# WL_BPF.net
KiCad netlist of a schematic drawn in Altium Designer
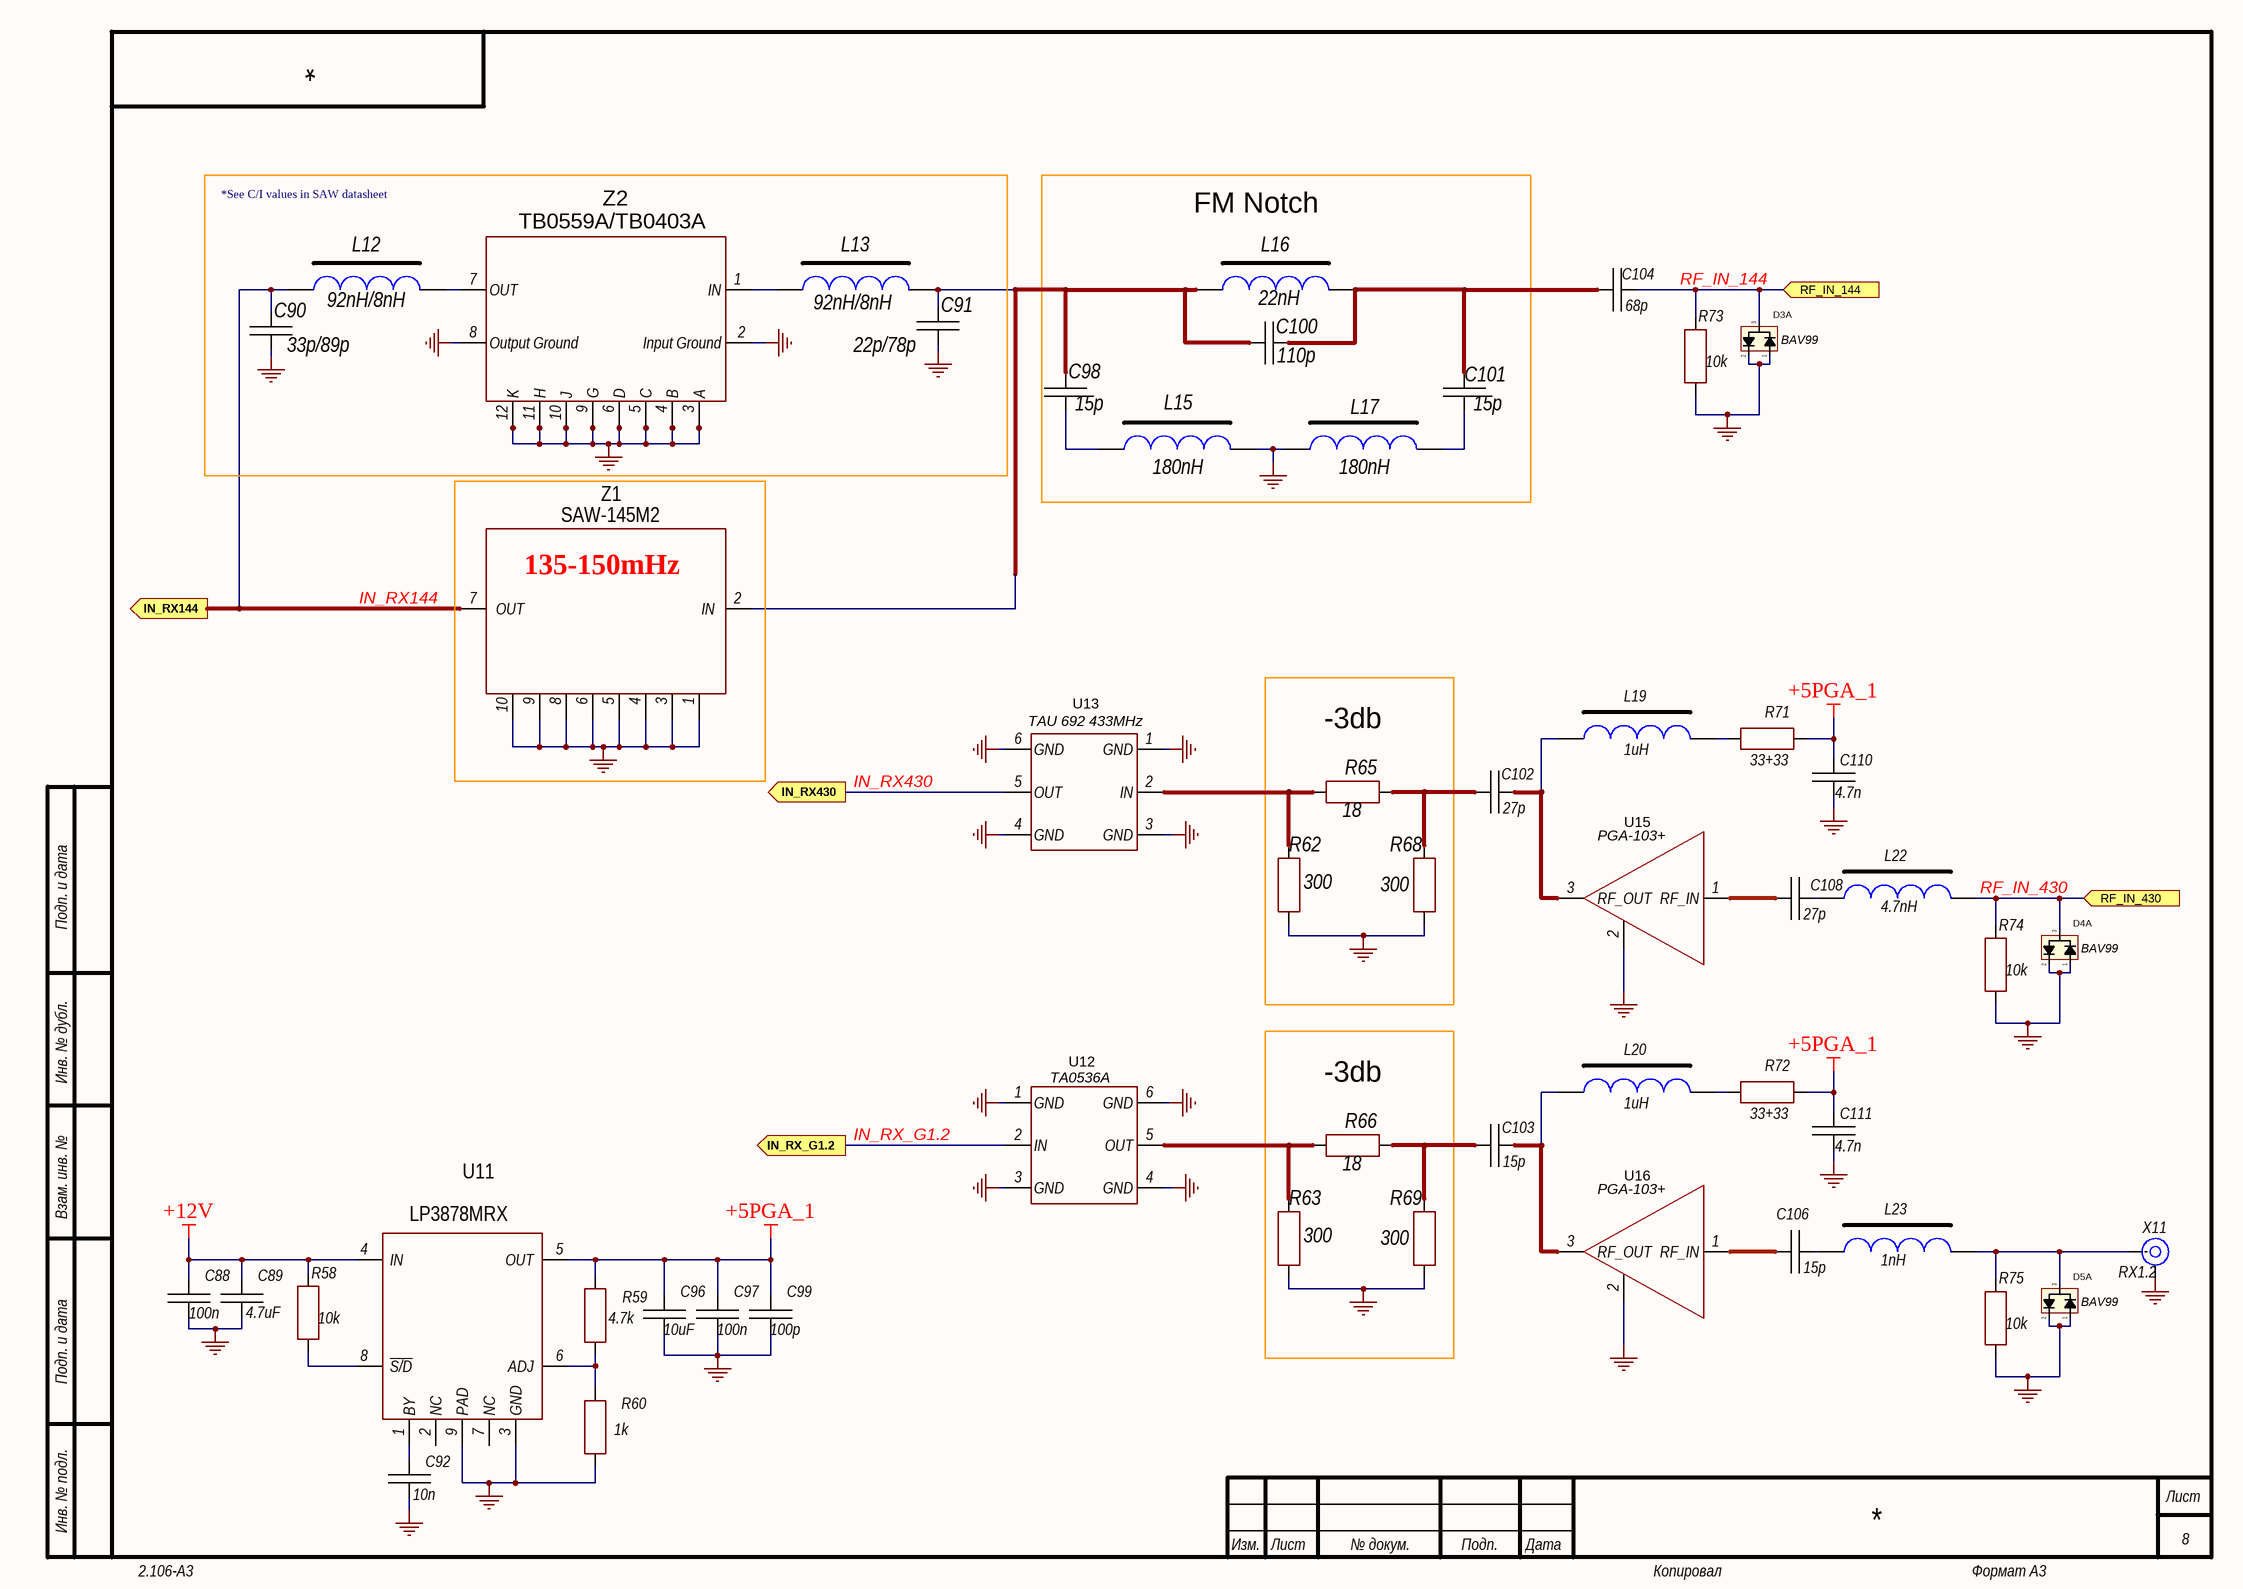
[diagram p0: WL_BPF.SchDoc]

(export (version "E")
  (design (tool "Eeschema 10.0.6"))
  (components
    (comp (ref "C88")
      (value "100n")
      (footprint "standard:CH0805C")
      (libsource (lib "Discrete") (part "Capacitor"))
    )
    (comp (ref "C89")
      (value "4.7uF")
      (footprint "standard:CH0805C")
      (libsource (lib "Discrete") (part "Capacitor"))
    )
    (comp (ref "C90")
      (value "33p/89p")
      (footprint "standard:CH0805C")
      (libsource (lib "Discrete") (part "Capacitor"))
    )
    (comp (ref "C91")
      (value "22p/78p")
      (footprint "standard:CH0805C")
      (libsource (lib "Discrete") (part "Capacitor"))
    )
    (comp (ref "C92")
      (value "10n")
      (footprint "standard:CH0805C")
      (libsource (lib "Discrete") (part "Capacitor"))
    )
    (comp (ref "C96")
      (value "10uF")
      (footprint "standard:CH0805C")
      (libsource (lib "Discrete") (part "Capacitor"))
    )
    (comp (ref "C97")
      (value "100n")
      (footprint "standard:CH0805C")
      (libsource (lib "Discrete") (part "Capacitor"))
    )
    (comp (ref "C98")
      (value "15p")
      (footprint "standard:CH0805C")
      (libsource (lib "Discrete") (part "Capacitor"))
    )
    (comp (ref "C99")
      (value "100p")
      (footprint "standard:CH0805C")
      (libsource (lib "Discrete") (part "Capacitor"))
    )
    (comp (ref "C100")
      (value "110p")
      (footprint "standard:CH0805C")
      (libsource (lib "Discrete") (part "Capacitor"))
    )
    (comp (ref "C101")
      (value "15p")
      (footprint "standard:CH0805C")
      (libsource (lib "Discrete") (part "Capacitor"))
    )
    (comp (ref "C102")
      (value "27p")
      (footprint "standard:CH0805C")
      (libsource (lib "Discrete") (part "Capacitor"))
    )
    (comp (ref "C103") (value "15p") (footprint "standard:CH0603C") (libsource (lib "") (part "Capacitor_1")))
    (comp (ref "C104")
      (value "68p")
      (footprint "standard:CH0805C")
      (libsource (lib "Discrete") (part "Capacitor"))
    )
    (comp (ref "C106") (value "15p") (footprint "standard:CH0603C") (libsource (lib "") (part "Capacitor_1")))
    (comp (ref "C108")
      (value "27p")
      (footprint "standard:CH0805C")
      (libsource (lib "Discrete") (part "Capacitor"))
    )
    (comp (ref "C110")
      (value "4.7n")
      (footprint "standard:CH0805C")
      (libsource (lib "Discrete") (part "Capacitor"))
    )
    (comp (ref "C111")
      (value "4.7n")
      (footprint "standard:CH0805C")
      (libsource (lib "Discrete") (part "Capacitor"))
    )
    (comp (ref "D3") (value "BAV99") (footprint "SOT23_132") (libsource (lib "Analog") (part "BAV99")))
    (comp (ref "D4") (value "BAV99") (footprint "SOT23_132") (libsource (lib "Analog") (part "BAV99")))
    (comp (ref "D5") (value "BAV99") (footprint "SOT23_132") (libsource (lib "Analog") (part "BAV99")))
    (comp (ref "L12") (value "92nH/8nH") (footprint "L1210") (libsource (lib "Transformers") (part "TRANS")))
    (comp (ref "L13") (value "92nH/8nH") (footprint "L1210") (libsource (lib "Transformers") (part "TRANS")))
    (comp (ref "L15") (value "180nH") (footprint "L1210") (libsource (lib "Transformers") (part "TRANS")))
    (comp (ref "L16") (value "22nH") (footprint "L1210") (libsource (lib "Transformers") (part "TRANS")))
    (comp (ref "L17") (value "180nH") (footprint "L1210") (libsource (lib "Transformers") (part "TRANS")))
    (comp (ref "L19") (value "1uH") (footprint "L1210") (libsource (lib "") (part "TRANS_1")))
    (comp (ref "L20") (value "1uH") (footprint "L1210") (libsource (lib "") (part "TRANS_1")))
    (comp (ref "L22") (value "4.7nH") (footprint "L1210") (libsource (lib "") (part "TRANS_1")))
    (comp (ref "L23") (value "1nH") (footprint "L1210") (libsource (lib "") (part "TRANS_1")))
    (comp (ref "R58") (value "10k") (footprint "standard:CH0805R") (libsource (lib "") (part "Resistor_1")))
    (comp (ref "R59") (value "4.7k") (footprint "standard:CH0805R") (libsource (lib "") (part "Resistor_1")))
    (comp (ref "R60") (value "1k") (footprint "standard:CH0805R") (libsource (lib "") (part "Resistor_1")))
    (comp (ref "R62") (value "300") (footprint "standard:CH0805R") (libsource (lib "") (part "Resistor_2")))
    (comp (ref "R63") (value "300") (footprint "standard:CH0603R") (libsource (lib "") (part "Resistor_2")))
    (comp (ref "R65") (value "18") (footprint "standard:CH0805R") (libsource (lib "") (part "Resistor_4")))
    (comp (ref "R66") (value "18") (footprint "standard:CH0603R") (libsource (lib "") (part "Resistor_3")))
    (comp (ref "R68") (value "300") (footprint "standard:CH0805R") (libsource (lib "") (part "Resistor_2")))
    (comp (ref "R69") (value "300") (footprint "standard:CH0603R") (libsource (lib "") (part "Resistor_2")))
    (comp (ref "R71")
      (value "33+33")
      (footprint "WL_RFFC:CH1206R")
      (libsource (lib "Discrete") (part "Resistor"))
    )
    (comp (ref "R72")
      (value "33+33")
      (footprint "WL_RFFC:CH1206R")
      (libsource (lib "Discrete") (part "Resistor"))
    )
    (comp (ref "R73") (value "10k") (footprint "standard:CH0805R") (libsource (lib "") (part "Resistor_1")))
    (comp (ref "R74") (value "10k") (footprint "standard:CH0805R") (libsource (lib "") (part "Resistor_1")))
    (comp (ref "R75") (value "10k") (footprint "standard:CH0805R") (libsource (lib "") (part "Resistor_5")))
    (comp (ref "U11")
      (value "LP3878MRX")
      (footprint "8-SOIC (PAD)")
      (libsource (lib "Power Supplies") (part "LP3878"))
    )
    (comp (ref "U12") (value "TA0536A") (footprint "MA08803") (libsource (lib "") (part "TAU692_1")))
    (comp (ref "U13")
      (value "TAU 692 433MHz")
      (footprint "TAU692")
      (libsource (lib "Digital") (part "TAU692"))
    )
    (comp (ref "U15")
      (value "PGA-103+")
      (footprint "SOT89_123")
      (libsource (lib "Digital") (part "PGA-103+"))
    )
    (comp (ref "U16")
      (value "PGA-103+")
      (footprint "SOT89_123")
      (libsource (lib "Digital") (part "PGA-103+"))
    )
    (comp (ref "X11")
      (value "RX1.2")
      (footprint "CON: u.Fl")
      (description "RF")
      (libsource (lib "Connectors") (part "SMA"))
    )
    (comp (ref "Z1") (value "SAW-145M2") (footprint "PAV") (libsource (lib "Module") (part "SXBP_PAW")))
    (comp (ref "Z2")
      (value "TB0559A/TB0403A")
      (footprint "TB0559A/TB0403A")
      (libsource (lib "Module") (part "TB0559A/TB0403A"))
    )
  )
  (nets
    (net (code "1") (name "+5PGA_1") (class "Default")
      (node (ref "C110") (pin "2") (pinfunction "2_2") (pintype "power_in"))
      (node (ref "C111") (pin "2") (pinfunction "2_2") (pintype "power_in"))
      (node (ref "C96") (pin "2") (pinfunction "2_2") (pintype "power_in"))
      (node (ref "C97") (pin "2") (pinfunction "2_2") (pintype "power_in"))
      (node (ref "C99") (pin "2") (pinfunction "2_2") (pintype "power_in"))
      (node (ref "R59") (pin "2") (pinfunction "2_2") (pintype "passive"))
      (node (ref "R71") (pin "2") (pinfunction "2_2") (pintype "passive"))
      (node (ref "R72") (pin "2") (pinfunction "2_2") (pintype "passive"))
      (node (ref "U11") (pin "5") (pinfunction "OUT_5") (pintype "power_in"))
    )
    (net (code "2") (name "+12V") (class "Default")
      (node (ref "C88") (pin "2") (pinfunction "2_2") (pintype "power_in"))
      (node (ref "C89") (pin "2") (pinfunction "2_2") (pintype "power_in"))
      (node (ref "R58") (pin "2") (pinfunction "2_2") (pintype "passive"))
      (node (ref "U11") (pin "4") (pinfunction "IN_4") (pintype "power_in"))
    )
    (net (code "3") (name "/IN_RX144") (class "Default")
      (node (ref "C90") (pin "2") (pinfunction "2_2") (pintype "power_in"))
      (node (ref "L12") (pin "1") (pinfunction "1_1") (pintype "passive"))
      (node (ref "Z1") (pin "7") (pinfunction "OUT_7") (pintype "passive"))
    )
    (net (code "4") (name "/IN_RX430") (class "Default")
      (node (ref "U13") (pin "5") (pinfunction "OUT_5") (pintype "passive"))
    )
    (net (code "5") (name "/IN_RX_G1.2") (class "Default")
      (node (ref "U12") (pin "2") (pinfunction "IN_2") (pintype "passive"))
    )
    (net (code "6") (name "/RF_IN_144") (class "Default")
      (node (ref "C104") (pin "2") (pinfunction "2_2") (pintype "power_in"))
      (node (ref "D3") (pin "3") (pinfunction "9_3") (pintype "passive"))
      (node (ref "R73") (pin "2") (pinfunction "2_2") (pintype "passive"))
    )
    (net (code "7") (name "/RF_IN_430") (class "Default")
      (node (ref "D4") (pin "3") (pinfunction "9_3") (pintype "passive"))
      (node (ref "L22") (pin "1") (pinfunction "1_1") (pintype "power_in"))
      (node (ref "R74") (pin "2") (pinfunction "2_2") (pintype "passive"))
    )
    (net (code "8") (name "GND") (class "Default")
      (node (ref "C110") (pin "1") (pinfunction "1_1") (pintype "passive"))
      (node (ref "C111") (pin "1") (pinfunction "1_1") (pintype "passive"))
      (node (ref "C88") (pin "1") (pinfunction "1_1") (pintype "passive"))
      (node (ref "C89") (pin "1") (pinfunction "1_1") (pintype "passive"))
      (node (ref "C90") (pin "1") (pinfunction "1_1") (pintype "passive"))
      (node (ref "C91") (pin "1") (pinfunction "1_1") (pintype "passive"))
      (node (ref "C92") (pin "1") (pinfunction "1_1") (pintype "passive"))
      (node (ref "C96") (pin "1") (pinfunction "1_1") (pintype "passive"))
      (node (ref "C97") (pin "1") (pinfunction "1_1") (pintype "passive"))
      (node (ref "C99") (pin "1") (pinfunction "1_1") (pintype "passive"))
      (node (ref "D3") (pin "1") (pinfunction "11_1") (pintype "passive"))
      (node (ref "D3") (pin "2") (pinfunction "10_2") (pintype "passive"))
      (node (ref "D4") (pin "1") (pinfunction "11_1") (pintype "passive"))
      (node (ref "D4") (pin "2") (pinfunction "10_2") (pintype "passive"))
      (node (ref "D5") (pin "1") (pinfunction "11_1") (pintype "passive"))
      (node (ref "D5") (pin "2") (pinfunction "10_2") (pintype "passive"))
      (node (ref "L15") (pin "2") (pinfunction "2_2") (pintype "passive"))
      (node (ref "L17") (pin "1") (pinfunction "1_1") (pintype "passive"))
      (node (ref "R60") (pin "1") (pinfunction "1_1") (pintype "passive"))
      (node (ref "R62") (pin "2") (pinfunction "2_2") (pintype "passive"))
      (node (ref "R63") (pin "2") (pinfunction "2_2") (pintype "passive"))
      (node (ref "R68") (pin "2") (pinfunction "2_2") (pintype "passive"))
      (node (ref "R69") (pin "2") (pinfunction "2_2") (pintype "passive"))
      (node (ref "R73") (pin "1") (pinfunction "1_1") (pintype "passive"))
      (node (ref "R74") (pin "1") (pinfunction "1_1") (pintype "passive"))
      (node (ref "R75") (pin "1") (pinfunction "1_1") (pintype "passive"))
      (node (ref "U11") (pin "3") (pinfunction "GND_3") (pintype "passive"))
      (node (ref "U11") (pin "9") (pinfunction "PAD_9") (pintype "passive"))
      (node (ref "U12") (pin "1") (pinfunction "GND_1") (pintype "passive"))
      (node (ref "U12") (pin "3") (pinfunction "GND_3") (pintype "passive"))
      (node (ref "U12") (pin "4") (pinfunction "GND_4") (pintype "passive"))
      (node (ref "U12") (pin "6") (pinfunction "GND_6") (pintype "passive"))
      (node (ref "U13") (pin "1") (pinfunction "GND_1") (pintype "passive"))
      (node (ref "U13") (pin "3") (pinfunction "GND_3") (pintype "passive"))
      (node (ref "U13") (pin "4") (pinfunction "GND_4") (pintype "passive"))
      (node (ref "U13") (pin "6") (pinfunction "GND_6") (pintype "passive"))
      (node (ref "U15") (pin "2") (pinfunction "GND_2") (pintype "passive"))
      (node (ref "U16") (pin "2") (pinfunction "GND_2") (pintype "passive"))
      (node (ref "X11") (pin "2") (pinfunction "IN_2") (pintype "passive"))
      (node (ref "Z1") (pin "1") (pinfunction "RESET_1") (pintype "passive"))
      (node (ref "Z1") (pin "10") (pinfunction "TXD_10") (pintype "passive"))
      (node (ref "Z1") (pin "3") (pinfunction "CH_PD_3") (pintype "passive"))
      (node (ref "Z1") (pin "4") (pinfunction "GPIO16_4") (pintype "passive"))
      (node (ref "Z1") (pin "5") (pinfunction "GPIO14_5") (pintype "passive"))
      (node (ref "Z1") (pin "6") (pinfunction "GPIO0_6") (pintype "passive"))
      (node (ref "Z1") (pin "8") (pinfunction "GPIO5_8") (pintype "passive"))
      (node (ref "Z1") (pin "9") (pinfunction "RXD_9") (pintype "passive"))
      (node (ref "Z2") (pin "10") (pinfunction "J_10") (pintype "passive"))
      (node (ref "Z2") (pin "11") (pinfunction "H_11") (pintype "passive"))
      (node (ref "Z2") (pin "12") (pinfunction "K_12") (pintype "passive"))
      (node (ref "Z2") (pin "2") (pinfunction "Input_Ground_2") (pintype "passive"))
      (node (ref "Z2") (pin "3") (pinfunction "A_3") (pintype "passive"))
      (node (ref "Z2") (pin "4") (pinfunction "B_4") (pintype "passive"))
      (node (ref "Z2") (pin "5") (pinfunction "C_5") (pintype "passive"))
      (node (ref "Z2") (pin "6") (pinfunction "D_6") (pintype "passive"))
      (node (ref "Z2") (pin "8") (pinfunction "Output_Ground_8") (pintype "passive"))
      (node (ref "Z2") (pin "9") (pinfunction "G_9") (pintype "passive"))
    )
    (net (code "9") (name "Net-(C98-Pad1)") (class "Default")
      (node (ref "C98") (pin "1") (pinfunction "1_1") (pintype "passive"))
      (node (ref "L15") (pin "1") (pinfunction "1_1") (pintype "passive"))
    )
    (net (code "10") (name "Net-(C100-Pad2)") (class "Default")
      (node (ref "C100") (pin "2") (pinfunction "2_2") (pintype "power_in"))
      (node (ref "C101") (pin "2") (pinfunction "2_2") (pintype "power_in"))
      (node (ref "C104") (pin "1") (pinfunction "1_1") (pintype "passive"))
      (node (ref "L16") (pin "2") (pinfunction "2_2") (pintype "passive"))
    )
    (net (code "11") (name "Net-(C101-Pad1)") (class "Default")
      (node (ref "C101") (pin "1") (pinfunction "1_1") (pintype "passive"))
      (node (ref "L17") (pin "2") (pinfunction "2_2") (pintype "passive"))
    )
    (net (code "12") (name "Net-(C102-Pad1)") (class "Default")
      (node (ref "C102") (pin "1") (pinfunction "1_1") (pintype "passive"))
      (node (ref "R65") (pin "1") (pinfunction "1_1") (pintype "passive"))
      (node (ref "R68") (pin "1") (pinfunction "1_1") (pintype "passive"))
    )
    (net (code "13") (name "Net-(C103-Pad1)") (class "Default")
      (node (ref "C103") (pin "1") (pinfunction "1_1") (pintype "passive"))
      (node (ref "R66") (pin "1") (pinfunction "1_1") (pintype "passive"))
      (node (ref "R69") (pin "1") (pinfunction "1_1") (pintype "passive"))
    )
    (net (code "14") (name "Net-(C106-Pad2)") (class "Default")
      (node (ref "C106") (pin "2") (pinfunction "2_2") (pintype "passive"))
      (node (ref "L23") (pin "2") (pinfunction "2_2") (pintype "power_in"))
    )
    (net (code "15") (name "Net-(C108-Pad2)") (class "Default")
      (node (ref "C108") (pin "2") (pinfunction "2_2") (pintype "power_in"))
      (node (ref "L22") (pin "2") (pinfunction "2_2") (pintype "power_in"))
    )
    (net (code "16") (name "Net-(D5A-9)") (class "Default")
      (node (ref "D5") (pin "3") (pinfunction "9_3") (pintype "passive"))
      (node (ref "L23") (pin "1") (pinfunction "1_1") (pintype "power_in"))
      (node (ref "R75") (pin "2") (pinfunction "2_2") (pintype "passive"))
      (node (ref "X11") (pin "1") (pinfunction "IN_1") (pintype "passive"))
    )
    (net (code "17") (name "Net-(L19-Pad1)") (class "Default")
      (node (ref "L19") (pin "1") (pinfunction "1_1") (pintype "power_in"))
      (node (ref "R71") (pin "1") (pinfunction "1_1") (pintype "passive"))
    )
    (net (code "18") (name "Net-(L20-Pad1)") (class "Default")
      (node (ref "L20") (pin "1") (pinfunction "1_1") (pintype "power_in"))
      (node (ref "R72") (pin "1") (pinfunction "1_1") (pintype "passive"))
    )
    (net (code "19") (name "Net-(U11-ADJ)") (class "Default")
      (node (ref "R59") (pin "1") (pinfunction "1_1") (pintype "passive"))
      (node (ref "R60") (pin "2") (pinfunction "2_2") (pintype "passive"))
      (node (ref "U11") (pin "6") (pinfunction "ADJ_6") (pintype "passive"))
    )
    (net (code "20") (name "Net-(U11-BY)") (class "Default")
      (node (ref "C92") (pin "2") (pinfunction "2_2") (pintype "power_in"))
      (node (ref "U11") (pin "1") (pinfunction "BY_1") (pintype "passive"))
    )
    (net (code "21") (name "Net-(U11-~{S{slash}D})") (class "Default")
      (node (ref "R58") (pin "1") (pinfunction "1_1") (pintype "passive"))
      (node (ref "U11") (pin "8") (pinfunction "~{S/D}_8") (pintype "power_in"))
    )
    (net (code "22") (name "Net-(U12-OUT)") (class "Default")
      (node (ref "R63") (pin "1") (pinfunction "1_1") (pintype "passive"))
      (node (ref "R66") (pin "2") (pinfunction "2_2") (pintype "passive"))
      (node (ref "U12") (pin "5") (pinfunction "OUT_5") (pintype "passive"))
    )
    (net (code "23") (name "Net-(U13-IN)") (class "Default")
      (node (ref "R62") (pin "1") (pinfunction "1_1") (pintype "passive"))
      (node (ref "R65") (pin "2") (pinfunction "2_2") (pintype "passive"))
      (node (ref "U13") (pin "2") (pinfunction "IN_2") (pintype "passive"))
    )
    (net (code "24") (name "Net-(U15-RF_IN)") (class "Default")
      (node (ref "C108") (pin "1") (pinfunction "1_1") (pintype "passive"))
      (node (ref "U15") (pin "1") (pinfunction "RF_IN_1") (pintype "passive"))
    )
    (net (code "25") (name "Net-(U15-RF_OUT)") (class "Default")
      (node (ref "C102") (pin "2") (pinfunction "2_2") (pintype "power_in"))
      (node (ref "L19") (pin "2") (pinfunction "2_2") (pintype "power_in"))
      (node (ref "U15") (pin "3") (pinfunction "RF_OUT_3") (pintype "passive"))
    )
    (net (code "26") (name "Net-(U16-RF_IN)") (class "Default")
      (node (ref "C106") (pin "1") (pinfunction "1_1") (pintype "passive"))
      (node (ref "U16") (pin "1") (pinfunction "RF_IN_1") (pintype "passive"))
    )
    (net (code "27") (name "Net-(U16-RF_OUT)") (class "Default")
      (node (ref "C103") (pin "2") (pinfunction "2_2") (pintype "passive"))
      (node (ref "L20") (pin "2") (pinfunction "2_2") (pintype "power_in"))
      (node (ref "U16") (pin "3") (pinfunction "RF_OUT_3") (pintype "passive"))
    )
    (net (code "28") (name "Net-(Z1-IN)") (class "Default")
      (node (ref "C100") (pin "1") (pinfunction "1_1") (pintype "passive"))
      (node (ref "C91") (pin "2") (pinfunction "2_2") (pintype "power_in"))
      (node (ref "C98") (pin "2") (pinfunction "2_2") (pintype "power_in"))
      (node (ref "L13") (pin "2") (pinfunction "2_2") (pintype "passive"))
      (node (ref "L16") (pin "1") (pinfunction "1_1") (pintype "passive"))
      (node (ref "Z1") (pin "2") (pinfunction "IN_2") (pintype "passive"))
    )
    (net (code "29") (name "Net-(Z2-IN)") (class "Default")
      (node (ref "L13") (pin "1") (pinfunction "1_1") (pintype "passive"))
      (node (ref "Z2") (pin "1") (pinfunction "IN_1") (pintype "passive"))
    )
    (net (code "30") (name "Net-(Z2-OUT)") (class "Default")
      (node (ref "L12") (pin "2") (pinfunction "2_2") (pintype "passive"))
      (node (ref "Z2") (pin "7") (pinfunction "OUT_7") (pintype "passive"))
    )
    (net (code "31") (name "unconnected-(U11-NC-Pad2)") (class "Default")
      (node (ref "U11") (pin "2") (pinfunction "NC_2") (pintype "passive"))
    )
    (net (code "32") (name "unconnected-(U11-NC-Pad7)") (class "Default")
      (node (ref "U11") (pin "7") (pinfunction "NC_7") (pintype "passive"))
    )
  )
)
